# EMI_filter.net
KiCad netlist of a schematic drawn in EAGLE
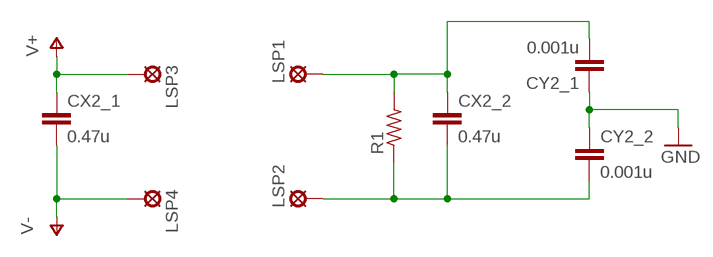
[diagram p0: schematic, sheet 1]

(export (version "E")
  (design (tool "Eeschema 10.0.6"))
  (components
    (comp (ref "CX2_1")
      (value "0.47u")
      (footprint "eagle-import:C150-091X182")
      (libsource (lib "eagle-import") (part "C-EU150-091X182"))
    )
    (comp (ref "CX2_2")
      (value "0.47u")
      (footprint "eagle-import:C150-091X182")
      (libsource (lib "eagle-import") (part "C-EU150-091X182"))
    )
    (comp (ref "CY2_1")
      (value "0.001u")
      (footprint "eagle-import:C102-043X133")
      (libsource (lib "eagle-import") (part "C-EU102-043X133"))
    )
    (comp (ref "CY2_2")
      (value "0.001u")
      (footprint "eagle-import:C102-043X133")
      (libsource (lib "eagle-import") (part "C-EU102-043X133"))
    )
    (comp (ref "LSP1")
      (value "SE14")
      (footprint "eagle-import:SE14")
      (libsource (lib "eagle-import") (part "SE14"))
    )
    (comp (ref "LSP2")
      (value "SE14")
      (footprint "eagle-import:SE14")
      (libsource (lib "eagle-import") (part "SE14"))
    )
    (comp (ref "LSP3")
      (value "SE14")
      (footprint "eagle-import:SE14")
      (libsource (lib "eagle-import") (part "SE14"))
    )
    (comp (ref "LSP4")
      (value "SE14")
      (footprint "eagle-import:SE14")
      (libsource (lib "eagle-import") (part "SE14"))
    )
    (comp (ref "R1")
      (value "R-US_0617/22")
      (footprint "eagle-import:0617_22")
      (libsource (lib "eagle-import") (part "R-US_0617/22"))
    )
  )
  (nets
    (net (code "1") (name "GND") (class "Default")
      (node (ref "CY2_1") (pin "1") (pinfunction "1_1") (pintype "passive"))
      (node (ref "CY2_2") (pin "1") (pinfunction "1_1") (pintype "passive"))
    )
    (net (code "2") (name "Net-(CX2_2-Pad1)") (class "Default")
      (node (ref "CX2_2") (pin "1") (pinfunction "1_1") (pintype "passive"))
      (node (ref "CY2_1") (pin "2") (pinfunction "2_2") (pintype "passive"))
      (node (ref "LSP1") (pin "MP") (pinfunction "MP_MP") (pintype "passive"))
      (node (ref "R1") (pin "2") (pinfunction "2_2") (pintype "passive"))
    )
    (net (code "3") (name "Net-(CX2_2-Pad2)") (class "Default")
      (node (ref "CX2_2") (pin "2") (pinfunction "2_2") (pintype "passive"))
      (node (ref "CY2_2") (pin "2") (pinfunction "2_2") (pintype "passive"))
      (node (ref "LSP2") (pin "MP") (pinfunction "MP_MP") (pintype "passive"))
      (node (ref "R1") (pin "1") (pinfunction "1_1") (pintype "passive"))
    )
    (net (code "4") (name "V+") (class "Default")
      (node (ref "CX2_1") (pin "1") (pinfunction "1_1") (pintype "passive"))
      (node (ref "LSP3") (pin "MP") (pinfunction "MP_MP") (pintype "passive"))
    )
    (net (code "5") (name "V-") (class "Default")
      (node (ref "CX2_1") (pin "2") (pinfunction "2_2") (pintype "passive"))
      (node (ref "LSP4") (pin "MP") (pinfunction "MP_MP") (pintype "passive"))
    )
  )
)
